# PCB_LED_CALENDAR__SINGLE_YEAR_DIGIT.net
KiCad netlist of a schematic drawn in Altium Designer
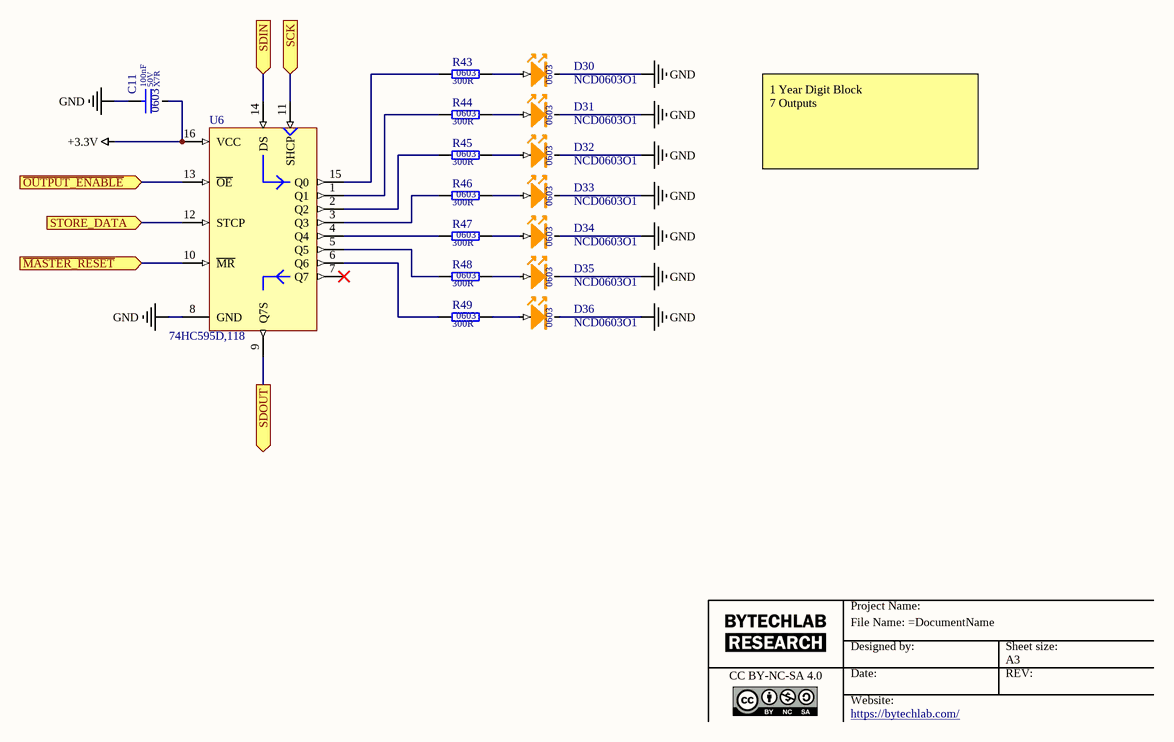
[diagram p0: PCB_LED_CALENDAR__SINGLE_YEAR_DIGIT.SchDoc]

(export (version "E")
  (design (tool "Eeschema 10.0.6"))
  (components
    (comp (ref "C11")
      (value "100nF")
      (footprint "C_0603_1608")
      (description "Capacitor")
      (fields
        (field (name "DIELECTRIC") "X7R")
        (field (name "VOLTAGE") "50V")
        (field (name "SCH_FOOTPRINT") "0603")
        (field (name "PART NUMBER") "C_100nF_50V_X7R_0603_5")
        (field (name "MANUFACTURER") "Samsung")
      )
      (libsource (lib "Library") (part "C"))
    )
    (comp (ref "D30")
      (value "NCD0603O1")
      (footprint "LED_0603")
      (description "Orange 130° 65mW 1.6V~2.6V 0603")
      (fields
        (field (name "MANUFACTURER") "Foshan NationStar Optoelectronics")
        (field (name "SCH_FOOTPRINT") "0603")
      )
      (libsource (lib "PCB_LED_CALENDAR") (part "OL_NCD0603O1"))
    )
    (comp (ref "D31")
      (value "NCD0603O1")
      (footprint "LED_0603")
      (description "Orange 130° 65mW 1.6V~2.6V 0603")
      (fields
        (field (name "MANUFACTURER") "Foshan NationStar Optoelectronics")
        (field (name "SCH_FOOTPRINT") "0603")
      )
      (libsource (lib "PCB_LED_CALENDAR") (part "OL_NCD0603O1"))
    )
    (comp (ref "D32")
      (value "NCD0603O1")
      (footprint "LED_0603")
      (description "Orange 130° 65mW 1.6V~2.6V 0603")
      (fields
        (field (name "MANUFACTURER") "Foshan NationStar Optoelectronics")
        (field (name "SCH_FOOTPRINT") "0603")
      )
      (libsource (lib "PCB_LED_CALENDAR") (part "OL_NCD0603O1"))
    )
    (comp (ref "D33")
      (value "NCD0603O1")
      (footprint "LED_0603")
      (description "Orange 130° 65mW 1.6V~2.6V 0603")
      (fields
        (field (name "MANUFACTURER") "Foshan NationStar Optoelectronics")
        (field (name "SCH_FOOTPRINT") "0603")
      )
      (libsource (lib "PCB_LED_CALENDAR") (part "OL_NCD0603O1"))
    )
    (comp (ref "D34")
      (value "NCD0603O1")
      (footprint "LED_0603")
      (description "Orange 130° 65mW 1.6V~2.6V 0603")
      (fields
        (field (name "MANUFACTURER") "Foshan NationStar Optoelectronics")
        (field (name "SCH_FOOTPRINT") "0603")
      )
      (libsource (lib "PCB_LED_CALENDAR") (part "OL_NCD0603O1"))
    )
    (comp (ref "D35")
      (value "NCD0603O1")
      (footprint "LED_0603")
      (description "Orange 130° 65mW 1.6V~2.6V 0603")
      (fields
        (field (name "MANUFACTURER") "Foshan NationStar Optoelectronics")
        (field (name "SCH_FOOTPRINT") "0603")
      )
      (libsource (lib "PCB_LED_CALENDAR") (part "OL_NCD0603O1"))
    )
    (comp (ref "D36")
      (value "NCD0603O1")
      (footprint "LED_0603")
      (description "Orange 130° 65mW 1.6V~2.6V 0603")
      (fields
        (field (name "MANUFACTURER") "Foshan NationStar Optoelectronics")
        (field (name "SCH_FOOTPRINT") "0603")
      )
      (libsource (lib "PCB_LED_CALENDAR") (part "OL_NCD0603O1"))
    )
    (comp (ref "R43")
      (value "300R")
      (footprint "R_0603_1608")
      (fields
        (field (name "SCH_FOOTPRINT") "0603")
        (field (name "PART NUMBER") "R_300R_0603_1")
        (field (name "VOLTAGE") "50V")
        (field (name "POWER") "100mW")
      )
      (libsource (lib "Library") (part "R"))
    )
    (comp (ref "R44")
      (value "300R")
      (footprint "R_0603_1608")
      (fields
        (field (name "SCH_FOOTPRINT") "0603")
        (field (name "PART NUMBER") "R_300R_0603_1")
        (field (name "VOLTAGE") "50V")
        (field (name "POWER") "100mW")
      )
      (libsource (lib "Library") (part "R"))
    )
    (comp (ref "R45")
      (value "300R")
      (footprint "R_0603_1608")
      (fields
        (field (name "SCH_FOOTPRINT") "0603")
        (field (name "PART NUMBER") "R_300R_0603_1")
        (field (name "VOLTAGE") "50V")
        (field (name "POWER") "100mW")
      )
      (libsource (lib "Library") (part "R"))
    )
    (comp (ref "R46")
      (value "300R")
      (footprint "R_0603_1608")
      (fields
        (field (name "SCH_FOOTPRINT") "0603")
        (field (name "PART NUMBER") "R_300R_0603_1")
        (field (name "VOLTAGE") "50V")
        (field (name "POWER") "100mW")
      )
      (libsource (lib "Library") (part "R"))
    )
    (comp (ref "R47")
      (value "300R")
      (footprint "R_0603_1608")
      (fields
        (field (name "SCH_FOOTPRINT") "0603")
        (field (name "PART NUMBER") "R_300R_0603_1")
        (field (name "VOLTAGE") "50V")
        (field (name "POWER") "100mW")
      )
      (libsource (lib "Library") (part "R"))
    )
    (comp (ref "R48")
      (value "300R")
      (footprint "R_0603_1608")
      (fields
        (field (name "SCH_FOOTPRINT") "0603")
        (field (name "PART NUMBER") "R_300R_0603_1")
        (field (name "VOLTAGE") "50V")
        (field (name "POWER") "100mW")
      )
      (libsource (lib "Library") (part "R"))
    )
    (comp (ref "R49")
      (value "300R")
      (footprint "R_0603_1608")
      (fields
        (field (name "SCH_FOOTPRINT") "0603")
        (field (name "PART NUMBER") "R_300R_0603_1")
        (field (name "VOLTAGE") "50V")
        (field (name "POWER") "100mW")
      )
      (libsource (lib "Library") (part "R"))
    )
    (comp (ref "U6")
      (value "74HC595D,118")
      (footprint "SO16")
      (description "8-bit serial-in, serial or parallel-out shift register with output latches; 3-state")
      (fields (field (name "MANUFACTURER") "Nexperia"))
      (libsource (lib "PCB_LED_CALENDAR") (part "U_74HC595D,118"))
    )
  )
  (nets
    (net (code "1") (name "+3.3V") (class "Default")
      (node (ref "C11") (pin "2") (pinfunction "2_2") (pintype "passive"))
      (node (ref "U6") (pin "16") (pinfunction "VCC_16") (pintype "input"))
    )
    (net (code "2") (name "/SCK") (class "Default")
      (node (ref "U6") (pin "11") (pinfunction "SHCP_11") (pintype "input"))
    )
    (net (code "3") (name "/SDIN") (class "Default")
      (node (ref "U6") (pin "14") (pinfunction "DS_14") (pintype "input"))
    )
    (net (code "4") (name "/SDOUT") (class "Default")
      (node (ref "U6") (pin "9") (pinfunction "Q7S_9") (pintype "output"))
    )
    (net (code "5") (name "/STORE_DATA") (class "Default")
      (node (ref "U6") (pin "12") (pinfunction "STCP_12") (pintype "input"))
    )
    (net (code "6") (name "/~{MASTER_RESET}") (class "Default")
      (node (ref "U6") (pin "10") (pinfunction "~{MR}_10") (pintype "input"))
    )
    (net (code "7") (name "/~{OUTPUT_ENABLE}") (class "Default")
      (node (ref "U6") (pin "13") (pinfunction "~{OE}_13") (pintype "input"))
    )
    (net (code "8") (name "GND") (class "Default")
      (node (ref "C11") (pin "1") (pinfunction "1_1") (pintype "passive"))
      (node (ref "D30") (pin "1") (pinfunction "K_1") (pintype "output"))
      (node (ref "D31") (pin "1") (pinfunction "K_1") (pintype "output"))
      (node (ref "D32") (pin "1") (pinfunction "K_1") (pintype "output"))
      (node (ref "D33") (pin "1") (pinfunction "K_1") (pintype "output"))
      (node (ref "D34") (pin "1") (pinfunction "K_1") (pintype "output"))
      (node (ref "D35") (pin "1") (pinfunction "K_1") (pintype "output"))
      (node (ref "D36") (pin "1") (pinfunction "K_1") (pintype "output"))
      (node (ref "U6") (pin "8") (pinfunction "GND_8") (pintype "power_in"))
    )
    (net (code "9") (name "Net-(D30-A)") (class "Default")
      (node (ref "D30") (pin "2") (pinfunction "A_2") (pintype "input"))
      (node (ref "R43") (pin "2") (pinfunction "2_2") (pintype "passive"))
    )
    (net (code "10") (name "Net-(D31-A)") (class "Default")
      (node (ref "D31") (pin "2") (pinfunction "A_2") (pintype "input"))
      (node (ref "R44") (pin "2") (pinfunction "2_2") (pintype "passive"))
    )
    (net (code "11") (name "Net-(D32-A)") (class "Default")
      (node (ref "D32") (pin "2") (pinfunction "A_2") (pintype "input"))
      (node (ref "R45") (pin "2") (pinfunction "2_2") (pintype "passive"))
    )
    (net (code "12") (name "Net-(D33-A)") (class "Default")
      (node (ref "D33") (pin "2") (pinfunction "A_2") (pintype "input"))
      (node (ref "R46") (pin "2") (pinfunction "2_2") (pintype "passive"))
    )
    (net (code "13") (name "Net-(D34-A)") (class "Default")
      (node (ref "D34") (pin "2") (pinfunction "A_2") (pintype "input"))
      (node (ref "R47") (pin "2") (pinfunction "2_2") (pintype "passive"))
    )
    (net (code "14") (name "Net-(D35-A)") (class "Default")
      (node (ref "D35") (pin "2") (pinfunction "A_2") (pintype "input"))
      (node (ref "R48") (pin "2") (pinfunction "2_2") (pintype "passive"))
    )
    (net (code "15") (name "Net-(D36-A)") (class "Default")
      (node (ref "D36") (pin "2") (pinfunction "A_2") (pintype "input"))
      (node (ref "R49") (pin "2") (pinfunction "2_2") (pintype "passive"))
    )
    (net (code "16") (name "Net-(U6-Q0)") (class "Default")
      (node (ref "R43") (pin "1") (pinfunction "1_1") (pintype "passive"))
      (node (ref "U6") (pin "15") (pinfunction "Q0_15") (pintype "output"))
    )
    (net (code "17") (name "Net-(U6-Q1)") (class "Default")
      (node (ref "R44") (pin "1") (pinfunction "1_1") (pintype "passive"))
      (node (ref "U6") (pin "1") (pinfunction "Q1_1") (pintype "output"))
    )
    (net (code "18") (name "Net-(U6-Q2)") (class "Default")
      (node (ref "R45") (pin "1") (pinfunction "1_1") (pintype "passive"))
      (node (ref "U6") (pin "2") (pinfunction "Q2_2") (pintype "output"))
    )
    (net (code "19") (name "Net-(U6-Q3)") (class "Default")
      (node (ref "R46") (pin "1") (pinfunction "1_1") (pintype "passive"))
      (node (ref "U6") (pin "3") (pinfunction "Q3_3") (pintype "output"))
    )
    (net (code "20") (name "Net-(U6-Q4)") (class "Default")
      (node (ref "R47") (pin "1") (pinfunction "1_1") (pintype "passive"))
      (node (ref "U6") (pin "4") (pinfunction "Q4_4") (pintype "output"))
    )
    (net (code "21") (name "Net-(U6-Q5)") (class "Default")
      (node (ref "R48") (pin "1") (pinfunction "1_1") (pintype "passive"))
      (node (ref "U6") (pin "5") (pinfunction "Q5_5") (pintype "output"))
    )
    (net (code "22") (name "Net-(U6-Q6)") (class "Default")
      (node (ref "R49") (pin "1") (pinfunction "1_1") (pintype "passive"))
      (node (ref "U6") (pin "6") (pinfunction "Q6_6") (pintype "output"))
    )
    (net (code "23") (name "unconnected-(U6-Q7-Pad7)") (class "Default")
      (node (ref "U6") (pin "7") (pinfunction "Q7_7") (pintype "output+no_connect"))
    )
  )
)
